# MainBoard_V100_MEM.net
KiCad netlist of a schematic drawn in Altium Designer
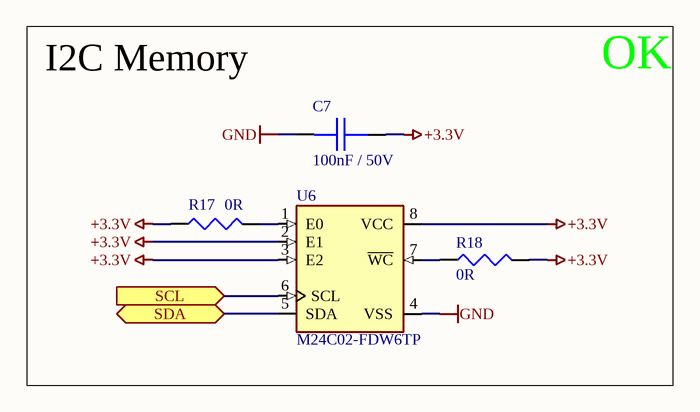
[diagram p0: MainBoard_V100_MEM.SchDoc]

(export (version "E")
  (design (tool "Eeschema 10.0.6"))
  (components
    (comp (ref "C7")
      (value "100nF / 50V")
      (footprint "0805_C")
      (description "100nF 50V X7R")
      (fields (field (name "PART NUMBER") "SMD0805-100nF-50V"))
      (libsource (lib "ALTIUM_DB_LIB") (part "CAP_NONPOL"))
    )
    (comp (ref "R17")
      (value "0R")
      (footprint "0805")
      (description "0R 0805 0.125W 5%")
      (fields (field (name "PART NUMBER") "0 R 5%"))
      (libsource (lib "ALTIUM_DB_LIB") (part "RESISTOR"))
    )
    (comp (ref "R18")
      (value "0R")
      (footprint "0805")
      (description "0R 0805 0.125W 5%")
      (fields (field (name "PART NUMBER") "0 R 5%"))
      (libsource (lib "ALTIUM_DB_LIB") (part "RESISTOR"))
    )
    (comp (ref "U6")
      (value "M24C02-FDW6TP")
      (footprint "TSSOP-8")
      (description "EEPROM Memory IC 2Kb (256 x 8) I2C 400kHz 900ns 8-TSSOP")
      (fields (field (name "MF") "STMicroelectronics") (field (name "DIGI-KEY_PART_NUMBER") "497-15746-1-ND"))
      (libsource (lib "ALTIUM_DB_LIB") (part "M24C02-FDW6TP"))
    )
  )
  (nets
    (net (code "1") (name "+3.3V") (class "Default")
      (node (ref "C7") (pin "2") (pintype "passive"))
      (node (ref "R17") (pin "1") (pintype "passive"))
      (node (ref "R18") (pin "2") (pintype "passive"))
      (node (ref "U6") (pin "2") (pinfunction "E1_2") (pintype "input"))
      (node (ref "U6") (pin "3") (pinfunction "E2_3") (pintype "input"))
      (node (ref "U6") (pin "8") (pinfunction "VCC_8") (pintype "power_in"))
    )
    (net (code "2") (name "/SCL") (class "Default")
      (node (ref "U6") (pin "6") (pinfunction "SCL_6") (pintype "input"))
    )
    (net (code "3") (name "/SDA") (class "Default")
      (node (ref "U6") (pin "5") (pinfunction "SDA_5") (pintype "bidirectional"))
    )
    (net (code "4") (name "GND") (class "Default")
      (node (ref "C7") (pin "1") (pintype "passive"))
      (node (ref "U6") (pin "4") (pinfunction "VSS_4") (pintype "power_in"))
    )
    (net (code "5") (name "Net-(U6-E0)") (class "Default")
      (node (ref "R17") (pin "2") (pintype "passive"))
      (node (ref "U6") (pin "1") (pinfunction "E0_1") (pintype "input"))
    )
    (net (code "6") (name "Net-(U6-~{WC})") (class "Default")
      (node (ref "R18") (pin "1") (pintype "passive"))
      (node (ref "U6") (pin "7") (pinfunction "~{WC}_7") (pintype "input"))
    )
  )
)
